# project2.net
KiCad netlist of a schematic drawn in Altium Designer
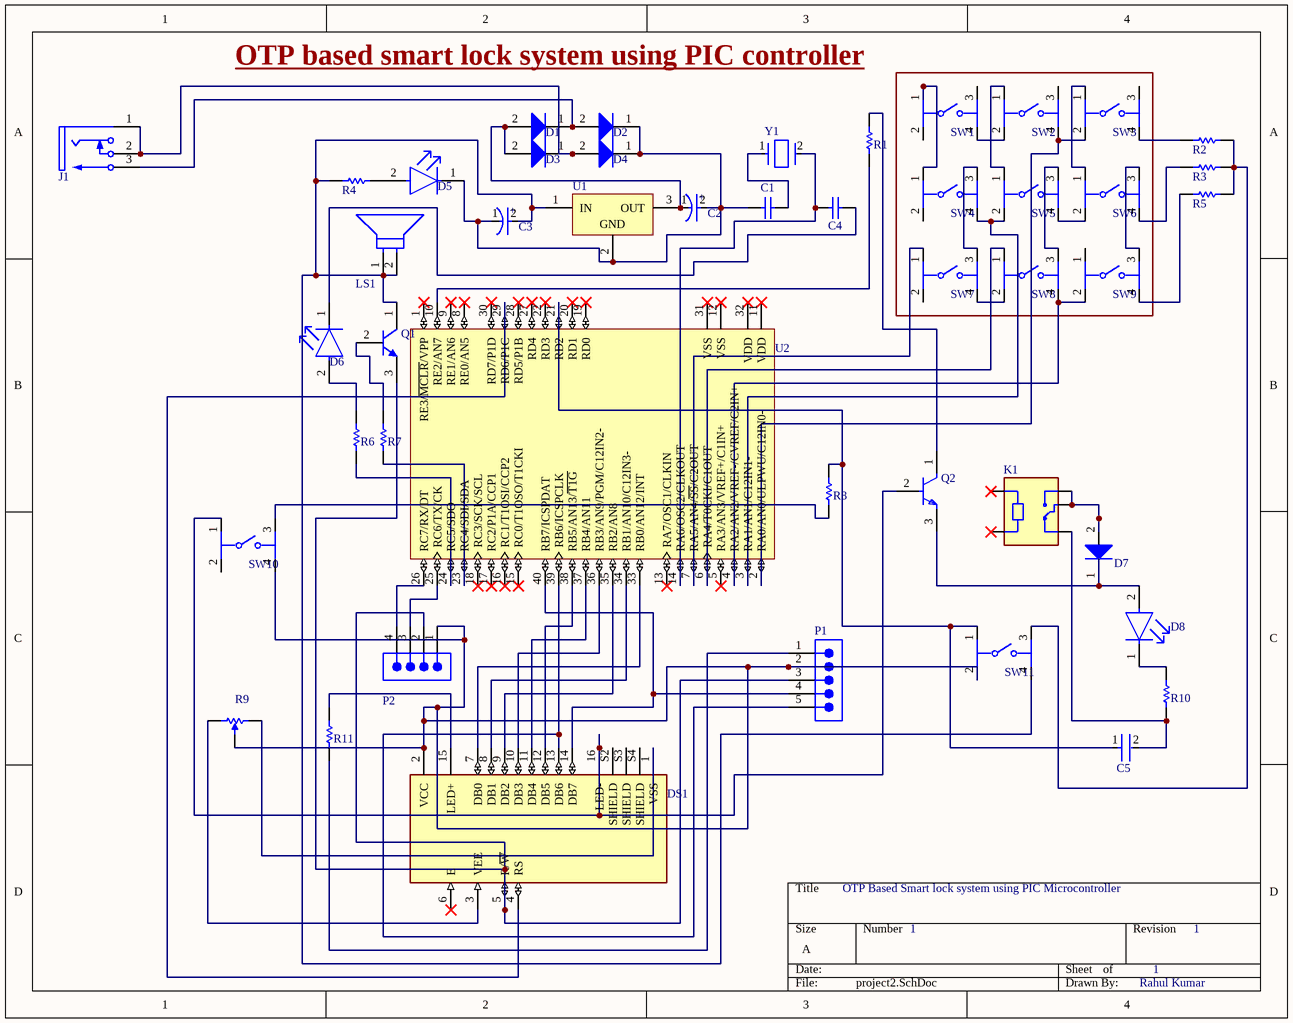
[diagram p0: project2.SchDoc]

(export (version "E")
  (design (tool "Eeschema 10.0.6"))
  (components
    (comp (ref "C1")
      (value "GRM188R71H102KA01D")
      (footprint "CAPC1608X90X35NL10T15")
      (fields (field (name "MANUFACTURER") "Murata"))
      (libsource (lib "Altium Content Vault") (part "CAP"))
    )
    (comp (ref "C2")
      (value "EEUFM1V221L")
      (footprint "FP-RAD-TH-D_8_0_5-L_15_1-MFG")
      (description "Aluminum Electrolytic Capacitors (Radial Lead Type) 220uF ±20% 35V")
      (fields (field (name "TOLERANCE") "20%") (field (name "VOLTAGE") "35V"))
      (libsource (lib "Altium Content Vault") (part "a00bbbee19879c290e62620ae7e47b1"))
    )
    (comp (ref "C3")
      (value "EEUHD1E101")
      (footprint "FP-RAD-TH-D_6_3_0_5-L_11-MFG")
      (description "Aluminum Electrolytic Capacitors (Radial Lead Type) AEC-Q200 Qualified 100uF ±20% 25V")
      (fields (field (name "TOLERANCE") "20%") (field (name "VOLTAGE") "25V"))
      (libsource (lib "Altium Content Vault") (part "a00bbbee19879c290e62620ae7e47b1"))
    )
    (comp (ref "C4")
      (value "GRM188R71H102KA01D")
      (footprint "CAPC1608X90X35NL10T15")
      (fields (field (name "MANUFACTURER") "Murata"))
      (libsource (lib "Altium Content Vault") (part "CAP"))
    )
    (comp (ref "C5")
      (value "06035A221JAT2A")
      (footprint "FP-0603-L_1_6_0_15-W_0_81-IPC_B")
      (description "General Purpose Ceramic Capacitor, 0603, 220pF, 5%, NP0, 30ppm/°C, 50V")
      (fields (field (name "TOLERANCE") "5%") (field (name "VOLTAGE") "50V"))
      (libsource (lib "Altium Content Vault") (part "02cd4be3c70576c341d710602a673aa"))
    )
    (comp (ref "D1")
      (value "BAT54HT1G")
      (footprint "ONSC-SOD-323-2-477-02_V")
      (description "Schottky Barrier Diode, 2-Pin SOD-323, Pb-Free, Tape and Reel")
      (fields (field (name "MANUFACTURER") "On Semiconductor"))
      (libsource (lib "Altium Content Vault") (part "ONSC-D-K1A2-2"))
    )
    (comp (ref "D2")
      (value "BAT54HT1G")
      (footprint "ONSC-SOD-323-2-477-02_V")
      (description "Schottky Barrier Diode, 2-Pin SOD-323, Pb-Free, Tape and Reel")
      (fields (field (name "MANUFACTURER") "On Semiconductor"))
      (libsource (lib "Altium Content Vault") (part "ONSC-D-K1A2-2"))
    )
    (comp (ref "D3")
      (value "BAT54HT1G")
      (footprint "ONSC-SOD-323-2-477-02_V")
      (description "Schottky Barrier Diode, 2-Pin SOD-323, Pb-Free, Tape and Reel")
      (fields (field (name "MANUFACTURER") "On Semiconductor"))
      (libsource (lib "Altium Content Vault") (part "ONSC-D-K1A2-2"))
    )
    (comp (ref "D4")
      (value "BAT54HT1G")
      (footprint "ONSC-SOD-323-2-477-02_V")
      (description "Schottky Barrier Diode, 2-Pin SOD-323, Pb-Free, Tape and Reel")
      (fields (field (name "MANUFACTURER") "On Semiconductor"))
      (libsource (lib "Altium Content Vault") (part "ONSC-D-K1A2-2"))
    )
    (comp (ref "D5")
      (value "LTST-C190GKT")
      (footprint "FP-LTST-C190GKT-MFG")
      (description "LED GREEN CLEAR CHIP SMD")
      (fields (field (name "VOLTAGE") "2V"))
      (libsource (lib "Altium Content Vault") (part "8706943c75ba83719d021d2fdc84c58"))
    )
    (comp (ref "D6")
      (value "LTST-C190GKT")
      (footprint "FP-LTST-C190GKT-MFG")
      (description "LED GREEN CLEAR CHIP SMD")
      (fields (field (name "VOLTAGE") "2V"))
      (libsource (lib "Altium Content Vault") (part "8706943c75ba83719d021d2fdc84c58"))
    )
    (comp (ref "D7")
      (value "BAT54HT1G")
      (footprint "ONSC-SOD-323-2-477-02_V")
      (description "Schottky Barrier Diode, 2-Pin SOD-323, Pb-Free, Tape and Reel")
      (fields (field (name "MANUFACTURER") "On Semiconductor"))
      (libsource (lib "Altium Content Vault") (part "ONSC-D-K1A2-2"))
    )
    (comp (ref "D8")
      (value "LTST-C190GKT")
      (footprint "FP-LTST-C190GKT-MFG")
      (description "LED GREEN CLEAR CHIP SMD")
      (fields (field (name "VOLTAGE") "2V"))
      (libsource (lib "Altium Content Vault") (part "8706943c75ba83719d021d2fdc84c58"))
    )
    (comp (ref "DS1")
      (value "RC1602B-BIW-CSV")
      (footprint "LCD_RC1602B-BIW-CSV")
      (description "Display: LCD; alphanumeric; STN Negative; 16x2; blue; LED; PIN: 16")
      (fields (field (name "MF") "Raystar"))
      (libsource (lib "RC1602B-BIW-CSV") (part "RC1602B-BIW-CSV"))
    )
    (comp (ref "J1")
      (value "RAPC712X")
      (footprint "SWITCH-RAPC712X-3_V")
      (description "Conn Powerjack Mini R/A PCMT, 5 A, 3-Pin THD, RoHS")
      (fields (field (name "MANUFACTURER") "Switchcraft"))
      (libsource (lib "Altium Content Vault") (part "SWITCH-RAPC712X-3"))
    )
    (comp (ref "K1")
      (value "SRD-05VDC-SL-C")
      (footprint "RELAY_SRD-05VDC-SL-C")
      (fields (field (name "MF") "Songle Relay"))
      (libsource (lib "SRD-05VDC-SL-C") (part "SRD-05VDC-SL-C"))
    )
    (comp (ref "LS1")
      (value "PKM17EPPH4001-B0")
      (footprint "FP-PKM17EPPH4001-B0-MFG")
      (description "AUDIO PIEZO TRANSDUCER 25V TH")
      (libsource (lib "Altium Content Vault") (part "5f581d31613f872430949aa526fd155"))
    )
    (comp (ref "P1")
      (value "653105124022")
      (footprint "653105124022")
      (libsource (lib "Altium Content Vault") (part "Header_Male_1R_05P"))
    )
    (comp (ref "P2")
      (value "679304124022")
      (footprint "679304124022")
      (libsource (lib "Altium Content Vault") (part "Header_Male_1R_04P"))
    )
    (comp (ref "Q1")
      (value "BC547B")
      (footprint "ONSC-TO-92-3-29-11")
      (description "Amplifier Transistor, NPN Silicon, 3-Pin TO-92, Bulk Box")
      (fields (field (name "MANUFACTURER") "On Semiconductor"))
      (libsource (lib "Altium Content Vault") (part "ONSC-NPN-C1B2E3-3"))
    )
    (comp (ref "Q2")
      (value "BC548")
      (footprint "FP-135AN-MFG")
      (description "BC548 Bulk Through Hole NPN Single Bipolar (BJT) Transistor 110 @ 2mA 5V 100mA 500mW 300MHz")
      (libsource (lib "Altium Content Vault") (part "0e34aa19c3f436cc9ae3cb3686437ec"))
    )
    (comp (ref "R1")
      (value "ERJ-8GEY0R00V")
      (footprint "RESC3216X70X50NL05T20")
      (fields (field (name "MANUFACTURER") "Panasonic"))
      (libsource (lib "Altium Content Vault") (part "RES"))
    )
    (comp (ref "R2")
      (value "ERJ-8GEY0R00V")
      (footprint "RESC3216X70X50NL05T20")
      (fields (field (name "MANUFACTURER") "Panasonic"))
      (libsource (lib "Altium Content Vault") (part "RES"))
    )
    (comp (ref "R3")
      (value "ERJ-8GEY0R00V")
      (footprint "RESC3216X70X50NL05T20")
      (fields (field (name "MANUFACTURER") "Panasonic"))
      (libsource (lib "Altium Content Vault") (part "RES"))
    )
    (comp (ref "R4")
      (value "ERJ-8GEY0R00V")
      (footprint "RESC3216X70X50NL05T20")
      (fields (field (name "MANUFACTURER") "Panasonic"))
      (libsource (lib "Altium Content Vault") (part "RES"))
    )
    (comp (ref "R5")
      (value "ERJ-8GEY0R00V")
      (footprint "RESC3216X70X50NL05T20")
      (fields (field (name "MANUFACTURER") "Panasonic"))
      (libsource (lib "Altium Content Vault") (part "RES"))
    )
    (comp (ref "R6")
      (value "ERJ-8GEY0R00V")
      (footprint "RESC3216X70X50NL05T20")
      (fields (field (name "MANUFACTURER") "Panasonic"))
      (libsource (lib "Altium Content Vault") (part "RES"))
    )
    (comp (ref "R7")
      (value "ERJ-8GEY0R00V")
      (footprint "RESC3216X70X50NL05T20")
      (fields (field (name "MANUFACTURER") "Panasonic"))
      (libsource (lib "Altium Content Vault") (part "RES"))
    )
    (comp (ref "R8")
      (value "ERJ-8GEY0R00V")
      (footprint "RESC3216X70X50NL05T20")
      (fields (field (name "MANUFACTURER") "Panasonic"))
      (libsource (lib "Altium Content Vault") (part "RES"))
    )
    (comp (ref "R9")
      (value "3296W-1-102LF")
      (footprint "BOUR-3296W-1-3")
      (description "Square Trimpot(R) Trimming Potentiometer, 1000 Ohm, -55 to 125 degC, 3-Pin THD, RoHS, Tube")
      (fields (field (name "TOLERANCE") "1%"))
      (libsource (lib "Altium Content Vault") (part "RES-ADJ-3"))
    )
    (comp (ref "R10")
      (value "ERJ-8GEY0R00V")
      (footprint "RESC3216X70X50NL05T20")
      (fields (field (name "MANUFACTURER") "Panasonic"))
      (libsource (lib "Altium Content Vault") (part "RES"))
    )
    (comp (ref "R11")
      (value "ERJ-8GEY0R00V")
      (footprint "RESC3216X70X50NL05T20")
      (fields (field (name "MANUFACTURER") "Panasonic"))
      (libsource (lib "Altium Content Vault") (part "RES"))
    )
    (comp (ref "SW1")
      (value "1-1825910-4")
      (footprint "FP-1-1825910-4-MFG")
      (description "SWITCH TACTILE SPST-NO 0.05A 24V")
      (fields
        (field (name "OCTOPART") "https://octopart.com/1-1825910-4-te+connectivity-42270468")
        (field (name "MANUFACTURER") "TE Connectivity")
      )
      (libsource (lib "Altium Content Vault") (part "b8895f3f4cefb76e1819d2863dba89b"))
    )
    (comp (ref "SW2")
      (value "1-1825910-4")
      (footprint "FP-1-1825910-4-MFG")
      (description "SWITCH TACTILE SPST-NO 0.05A 24V")
      (fields
        (field (name "OCTOPART") "https://octopart.com/1-1825910-4-te+connectivity-42270468")
        (field (name "MANUFACTURER") "TE Connectivity")
      )
      (libsource (lib "Altium Content Vault") (part "b8895f3f4cefb76e1819d2863dba89b"))
    )
    (comp (ref "SW3")
      (value "1-1825910-4")
      (footprint "FP-1-1825910-4-MFG")
      (description "SWITCH TACTILE SPST-NO 0.05A 24V")
      (fields
        (field (name "OCTOPART") "https://octopart.com/1-1825910-4-te+connectivity-42270468")
        (field (name "MANUFACTURER") "TE Connectivity")
      )
      (libsource (lib "Altium Content Vault") (part "b8895f3f4cefb76e1819d2863dba89b"))
    )
    (comp (ref "SW4")
      (value "1-1825910-4")
      (footprint "FP-1-1825910-4-MFG")
      (description "SWITCH TACTILE SPST-NO 0.05A 24V")
      (fields
        (field (name "OCTOPART") "https://octopart.com/1-1825910-4-te+connectivity-42270468")
        (field (name "MANUFACTURER") "TE Connectivity")
      )
      (libsource (lib "Altium Content Vault") (part "b8895f3f4cefb76e1819d2863dba89b"))
    )
    (comp (ref "SW5")
      (value "1-1825910-4")
      (footprint "FP-1-1825910-4-MFG")
      (description "SWITCH TACTILE SPST-NO 0.05A 24V")
      (fields
        (field (name "OCTOPART") "https://octopart.com/1-1825910-4-te+connectivity-42270468")
        (field (name "MANUFACTURER") "TE Connectivity")
      )
      (libsource (lib "Altium Content Vault") (part "b8895f3f4cefb76e1819d2863dba89b"))
    )
    (comp (ref "SW6")
      (value "1-1825910-4")
      (footprint "FP-1-1825910-4-MFG")
      (description "SWITCH TACTILE SPST-NO 0.05A 24V")
      (fields
        (field (name "OCTOPART") "https://octopart.com/1-1825910-4-te+connectivity-42270468")
        (field (name "MANUFACTURER") "TE Connectivity")
      )
      (libsource (lib "Altium Content Vault") (part "b8895f3f4cefb76e1819d2863dba89b"))
    )
    (comp (ref "SW7")
      (value "1-1825910-4")
      (footprint "FP-1-1825910-4-MFG")
      (description "SWITCH TACTILE SPST-NO 0.05A 24V")
      (fields
        (field (name "OCTOPART") "https://octopart.com/1-1825910-4-te+connectivity-42270468")
        (field (name "MANUFACTURER") "TE Connectivity")
      )
      (libsource (lib "Altium Content Vault") (part "b8895f3f4cefb76e1819d2863dba89b"))
    )
    (comp (ref "SW8")
      (value "1-1825910-4")
      (footprint "FP-1-1825910-4-MFG")
      (description "SWITCH TACTILE SPST-NO 0.05A 24V")
      (fields
        (field (name "OCTOPART") "https://octopart.com/1-1825910-4-te+connectivity-42270468")
        (field (name "MANUFACTURER") "TE Connectivity")
      )
      (libsource (lib "Altium Content Vault") (part "b8895f3f4cefb76e1819d2863dba89b"))
    )
    (comp (ref "SW9")
      (value "1-1825910-4")
      (footprint "FP-1-1825910-4-MFG")
      (description "SWITCH TACTILE SPST-NO 0.05A 24V")
      (fields
        (field (name "OCTOPART") "https://octopart.com/1-1825910-4-te+connectivity-42270468")
        (field (name "MANUFACTURER") "TE Connectivity")
      )
      (libsource (lib "Altium Content Vault") (part "b8895f3f4cefb76e1819d2863dba89b"))
    )
    (comp (ref "SW10")
      (value "1-1825910-4")
      (footprint "FP-1-1825910-4-MFG")
      (description "SWITCH TACTILE SPST-NO 0.05A 24V")
      (fields
        (field (name "OCTOPART") "https://octopart.com/1-1825910-4-te+connectivity-42270468")
        (field (name "MANUFACTURER") "TE Connectivity")
      )
      (libsource (lib "Altium Content Vault") (part "b8895f3f4cefb76e1819d2863dba89b"))
    )
    (comp (ref "SW11")
      (value "1-1825910-4")
      (footprint "FP-1-1825910-4-MFG")
      (description "SWITCH TACTILE SPST-NO 0.05A 24V")
      (fields
        (field (name "OCTOPART") "https://octopart.com/1-1825910-4-te+connectivity-42270468")
        (field (name "MANUFACTURER") "TE Connectivity")
      )
      (libsource (lib "Altium Content Vault") (part "b8895f3f4cefb76e1819d2863dba89b"))
    )
    (comp (ref "U1")
      (value "L7805CV")
      (footprint "TO220")
      (description "Positive Voltage Regulator, 5V, 3-Pin TO-220")
      (libsource (lib "Altium Content Vault") (part "PM-REG-L4940-SIL3"))
    )
    (comp (ref "U2")
      (value "PIC16F887-I/P")
      (footprint "PDIP600-P40")
      (libsource (lib "Altium Content Vault") (part "MC-8B-16F884-IL40"))
    )
    (comp (ref "Y1")
      (value "ABLS-8.000MHZ-B2-T")
      (footprint "FP-ABLS-MFG")
      (description "CRYSTAL 8.0000MHZ 18PF SMD")
      (fields (field (name "TOLERANCE") "20ppm"))
      (libsource (lib "Altium Content Vault") (part "c23a69dc6c9e2f18f2079038eb95dd1"))
    )
  )
  (nets
    (net (code "1") (name "Net-(C1-Pad2)") (class "Default")
      (node (ref "C1") (pin "2") (pinfunction "2_2") (pintype "passive"))
      (node (ref "Y1") (pin "1") (pinfunction "1_1") (pintype "passive"))
    )
    (net (code "2") (name "Net-(C2-A)") (class "Default")
      (node (ref "C1") (pin "1") (pinfunction "1_1") (pintype "passive"))
      (node (ref "C2") (pin "2") (pinfunction "A_2") (pintype "passive"))
      (node (ref "C3") (pin "1") (pinfunction "C_1") (pintype "passive"))
      (node (ref "D2") (pin "1") (pinfunction "K_1") (pintype "passive"))
      (node (ref "D4") (pin "1") (pinfunction "K_1") (pintype "passive"))
      (node (ref "D5") (pin "1") (pinfunction "C_1") (pintype "passive"))
      (node (ref "U1") (pin "2") (pinfunction "GND_2") (pintype "power_in"))
    )
    (net (code "3") (name "Net-(C2-C)") (class "Default")
      (node (ref "C2") (pin "1") (pinfunction "C_1") (pintype "passive"))
      (node (ref "D1") (pin "2") (pinfunction "A_2") (pintype "passive"))
      (node (ref "D3") (pin "2") (pinfunction "A_2") (pintype "passive"))
      (node (ref "U1") (pin "3") (pinfunction "OUT_3") (pintype "power_in"))
    )
    (net (code "4") (name "Net-(C3-A)") (class "Default")
      (node (ref "C3") (pin "2") (pinfunction "A_2") (pintype "passive"))
      (node (ref "LS1") (pin "1") (pinfunction "1_1") (pintype "passive"))
      (node (ref "LS1") (pin "2") (pinfunction "2_2") (pintype "passive"))
      (node (ref "Q1") (pin "1") (pinfunction "C_1") (pintype "passive"))
      (node (ref "R4") (pin "2") (pinfunction "2_2") (pintype "passive"))
      (node (ref "SW11") (pin "4") (pinfunction "4_4") (pintype "passive"))
      (node (ref "U1") (pin "1") (pinfunction "IN_1") (pintype "power_in"))
    )
    (net (code "5") (name "Net-(C5-Pad2)") (class "Default")
      (node (ref "C5") (pin "2") (pinfunction "2_2") (pintype "passive"))
      (node (ref "K1") (pin "NC") (pinfunction "NC_NC") (pintype "passive"))
      (node (ref "R10") (pin "1") (pinfunction "1_1") (pintype "passive"))
    )
    (net (code "6") (name "Net-(D1-K)") (class "Default")
      (node (ref "D1") (pin "1") (pinfunction "K_1") (pintype "passive"))
      (node (ref "D2") (pin "2") (pinfunction "A_2") (pintype "passive"))
      (node (ref "J1") (pin "3") (pinfunction "3_3") (pintype "passive"))
    )
    (net (code "7") (name "Net-(D3-K)") (class "Default")
      (node (ref "D3") (pin "1") (pinfunction "K_1") (pintype "passive"))
      (node (ref "D4") (pin "2") (pinfunction "A_2") (pintype "passive"))
      (node (ref "J1") (pin "1") (pinfunction "1_1") (pintype "passive"))
      (node (ref "J1") (pin "2") (pinfunction "2_2") (pintype "passive"))
    )
    (net (code "8") (name "Net-(D5-A)") (class "Default")
      (node (ref "D5") (pin "2") (pinfunction "A_2") (pintype "passive"))
      (node (ref "R4") (pin "1") (pinfunction "1_1") (pintype "passive"))
    )
    (net (code "9") (name "Net-(D6-A)") (class "Default")
      (node (ref "D6") (pin "2") (pinfunction "A_2") (pintype "passive"))
      (node (ref "R6") (pin "2") (pinfunction "2_2") (pintype "passive"))
    )
    (net (code "10") (name "Net-(D6-C)") (class "Default")
      (node (ref "C4") (pin "1") (pinfunction "1_1") (pintype "passive"))
      (node (ref "D6") (pin "1") (pinfunction "C_1") (pintype "passive"))
    )
    (net (code "11") (name "Net-(D7-A)") (class "Default")
      (node (ref "D7") (pin "2") (pinfunction "A_2") (pintype "passive"))
      (node (ref "K1") (pin "COM") (pinfunction "COM_COM") (pintype "passive"))
      (node (ref "K1") (pin "NO") (pinfunction "NO_NO") (pintype "passive"))
    )
    (net (code "12") (name "Net-(D7-K)") (class "Default")
      (node (ref "D7") (pin "1") (pinfunction "K_1") (pintype "passive"))
      (node (ref "D8") (pin "2") (pinfunction "A_2") (pintype "passive"))
      (node (ref "Q2") (pin "3") (pinfunction "E_3") (pintype "passive"))
    )
    (net (code "13") (name "Net-(D8-C)") (class "Default")
      (node (ref "D8") (pin "1") (pinfunction "C_1") (pintype "passive"))
      (node (ref "R10") (pin "2") (pinfunction "2_2") (pintype "passive"))
    )
    (net (code "14") (name "Net-(DS1-DB0)") (class "Default")
      (node (ref "DS1") (pin "7") (pinfunction "DB0_7") (pintype "bidirectional"))
      (node (ref "U2") (pin "33") (pinfunction "RB0/AN12/INT_33") (pintype "bidirectional"))
    )
    (net (code "15") (name "Net-(DS1-DB1)") (class "Default")
      (node (ref "DS1") (pin "8") (pinfunction "DB1_8") (pintype "bidirectional"))
      (node (ref "U2") (pin "34") (pinfunction "RB1/AN10/C12IN3-_34") (pintype "bidirectional"))
    )
    (net (code "16") (name "Net-(DS1-DB2)") (class "Default")
      (node (ref "DS1") (pin "9") (pinfunction "DB2_9") (pintype "bidirectional"))
      (node (ref "U2") (pin "35") (pinfunction "RB2/AN8_35") (pintype "bidirectional"))
    )
    (net (code "17") (name "Net-(DS1-DB3)") (class "Default")
      (node (ref "DS1") (pin "10") (pinfunction "DB3_10") (pintype "bidirectional"))
      (node (ref "U2") (pin "36") (pinfunction "RB3/AN9/PGM/C12IN2-_36") (pintype "bidirectional"))
    )
    (net (code "18") (name "Net-(DS1-DB4)") (class "Default")
      (node (ref "DS1") (pin "11") (pinfunction "DB4_11") (pintype "bidirectional"))
      (node (ref "U2") (pin "37") (pinfunction "RB4/AN11_37") (pintype "bidirectional"))
    )
    (net (code "19") (name "Net-(DS1-DB5)") (class "Default")
      (node (ref "DS1") (pin "12") (pinfunction "DB5_12") (pintype "bidirectional"))
      (node (ref "U2") (pin "38") (pinfunction "RB5/AN13/~{T1G}_38") (pintype "bidirectional"))
    )
    (net (code "20") (name "Net-(DS1-DB6)") (class "Default")
      (node (ref "DS1") (pin "13") (pinfunction "DB6_13") (pintype "bidirectional"))
      (node (ref "P1") (pin "5") (pinfunction "5_5") (pintype "passive"))
      (node (ref "U2") (pin "39") (pinfunction "RB6/ICSPCLK_39") (pintype "bidirectional"))
    )
    (net (code "21") (name "Net-(DS1-DB7)") (class "Default")
      (node (ref "DS1") (pin "14") (pinfunction "DB7_14") (pintype "bidirectional"))
      (node (ref "P1") (pin "4") (pinfunction "4_4") (pintype "passive"))
      (node (ref "U2") (pin "40") (pinfunction "RB7/ICSPDAT_40") (pintype "bidirectional"))
    )
    (net (code "22") (name "Net-(DS1-LED+)") (class "Default")
      (node (ref "DS1") (pin "15") (pinfunction "LED+_15") (pintype "power_in"))
      (node (ref "R11") (pin "2") (pinfunction "2_2") (pintype "passive"))
    )
    (net (code "23") (name "Net-(DS1-LED-)") (class "Default")
      (node (ref "DS1") (pin "16") (pinfunction "LED-_16") (pintype "power_in"))
      (node (ref "Q2") (pin "2") (pinfunction "B_2") (pintype "passive"))
      (node (ref "SW10") (pin "1") (pinfunction "1_1") (pintype "passive"))
    )
    (net (code "24") (name "Net-(DS1-RS)") (class "Default")
      (node (ref "DS1") (pin "4") (pinfunction "RS_4") (pintype "bidirectional"))
      (node (ref "U2") (pin "29") (pinfunction "RD6/P1C_29") (pintype "bidirectional"))
    )
    (net (code "25") (name "Net-(DS1-R{slash}~{W})") (class "Default")
      (node (ref "DS1") (pin "5") (pinfunction "R/~{W}_5") (pintype "bidirectional"))
      (node (ref "P1") (pin "3") (pinfunction "3_3") (pintype "passive"))
      (node (ref "P2") (pin "2") (pinfunction "2_2") (pintype "passive"))
      (node (ref "Q1") (pin "3") (pinfunction "E_3") (pintype "passive"))
    )
    (net (code "26") (name "Net-(DS1-VCC)") (class "Default")
      (node (ref "DS1") (pin "2") (pinfunction "VCC_2") (pintype "power_in"))
      (node (ref "P1") (pin "2") (pinfunction "2_2") (pintype "passive"))
      (node (ref "P2") (pin "1") (pinfunction "1_1") (pintype "passive"))
      (node (ref "R9") (pin "3") (pinfunction "TAP_3") (pintype "passive"))
      (node (ref "SW10") (pin "4") (pinfunction "4_4") (pintype "passive"))
      (node (ref "SW11") (pin "2") (pinfunction "2_2") (pintype "passive"))
    )
    (net (code "27") (name "Net-(DS1-VEE)") (class "Default")
      (node (ref "DS1") (pin "3") (pinfunction "VEE_3") (pintype "input"))
      (node (ref "R9") (pin "1") (pinfunction "A_1") (pintype "passive"))
    )
    (net (code "28") (name "Net-(DS1-VSS)") (class "Default")
      (node (ref "DS1") (pin "1") (pinfunction "VSS_1") (pintype "power_in"))
      (node (ref "R9") (pin "2") (pinfunction "B_2") (pintype "passive"))
    )
    (net (code "29") (name "Net-(P1-Pad1)") (class "Default")
      (node (ref "P1") (pin "1") (pinfunction "1_1") (pintype "passive"))
      (node (ref "R11") (pin "1") (pinfunction "1_1") (pintype "passive"))
    )
    (net (code "30") (name "Net-(Q1-B)") (class "Default")
      (node (ref "Q1") (pin "2") (pinfunction "B_2") (pintype "passive"))
      (node (ref "R7") (pin "2") (pinfunction "2_2") (pintype "passive"))
    )
    (net (code "31") (name "Net-(Q2-C)") (class "Default")
      (node (ref "Q2") (pin "1") (pinfunction "C_1") (pintype "passive"))
      (node (ref "R1") (pin "1") (pinfunction "1_1") (pintype "passive"))
    )
    (net (code "32") (name "Net-(R2-Pad1)") (class "Default")
      (node (ref "R2") (pin "1") (pinfunction "1_1") (pintype "passive"))
      (node (ref "R3") (pin "1") (pinfunction "1_1") (pintype "passive"))
      (node (ref "R5") (pin "1") (pinfunction "1_1") (pintype "passive"))
      (node (ref "SW11") (pin "3") (pinfunction "3_3") (pintype "passive"))
    )
    (net (code "33") (name "Net-(R2-Pad2)") (class "Default")
      (node (ref "R2") (pin "2") (pinfunction "2_2") (pintype "passive"))
      (node (ref "SW3") (pin "4") (pinfunction "4_4") (pintype "passive"))
    )
    (net (code "34") (name "Net-(R3-Pad2)") (class "Default")
      (node (ref "R3") (pin "2") (pinfunction "2_2") (pintype "passive"))
      (node (ref "SW6") (pin "4") (pinfunction "4_4") (pintype "passive"))
    )
    (net (code "35") (name "Net-(R5-Pad2)") (class "Default")
      (node (ref "R5") (pin "2") (pinfunction "2_2") (pintype "passive"))
      (node (ref "SW9") (pin "4") (pinfunction "4_4") (pintype "passive"))
    )
    (net (code "36") (name "Net-(R8-Pad1)") (class "Default")
      (node (ref "R8") (pin "1") (pinfunction "1_1") (pintype "passive"))
      (node (ref "SW10") (pin "3") (pinfunction "3_3") (pintype "passive"))
    )
    (net (code "37") (name "Net-(SW1-Pad1)") (class "Default")
      (node (ref "SW1") (pin "1") (pinfunction "1_1") (pintype "passive"))
      (node (ref "SW4") (pin "1") (pinfunction "1_1") (pintype "passive"))
    )
    (net (code "38") (name "Net-(SW1-Pad4)") (class "Default")
      (node (ref "SW1") (pin "4") (pinfunction "4_4") (pintype "passive"))
      (node (ref "SW2") (pin "2") (pinfunction "2_2") (pintype "passive"))
    )
    (net (code "39") (name "Net-(SW2-Pad1)") (class "Default")
      (node (ref "SW2") (pin "1") (pinfunction "1_1") (pintype "passive"))
      (node (ref "SW5") (pin "1") (pinfunction "1_1") (pintype "passive"))
    )
    (net (code "40") (name "Net-(SW3-Pad1)") (class "Default")
      (node (ref "SW3") (pin "1") (pinfunction "1_1") (pintype "passive"))
      (node (ref "SW6") (pin "1") (pinfunction "1_1") (pintype "passive"))
    )
    (net (code "41") (name "Net-(SW4-Pad3)") (class "Default")
      (node (ref "SW4") (pin "3") (pinfunction "3_3") (pintype "passive"))
      (node (ref "SW7") (pin "3") (pinfunction "3_3") (pintype "passive"))
    )
    (net (code "42") (name "Net-(SW5-Pad3)") (class "Default")
      (node (ref "SW5") (pin "3") (pinfunction "3_3") (pintype "passive"))
      (node (ref "SW8") (pin "3") (pinfunction "3_3") (pintype "passive"))
    )
    (net (code "43") (name "Net-(SW5-Pad4)") (class "Default")
      (node (ref "SW5") (pin "4") (pinfunction "4_4") (pintype "passive"))
      (node (ref "SW6") (pin "2") (pinfunction "2_2") (pintype "passive"))
    )
    (net (code "44") (name "Net-(SW6-Pad3)") (class "Default")
      (node (ref "SW6") (pin "3") (pinfunction "3_3") (pintype "passive"))
      (node (ref "SW9") (pin "3") (pinfunction "3_3") (pintype "passive"))
    )
    (net (code "45") (name "Net-(SW7-Pad4)") (class "Default")
      (node (ref "SW7") (pin "4") (pinfunction "4_4") (pintype "passive"))
      (node (ref "SW8") (pin "2") (pinfunction "2_2") (pintype "passive"))
    )
    (net (code "46") (name "Net-(U2-RA0{slash}AN0{slash}ULPWU{slash}C12IN0-)") (class "Default")
      (node (ref "SW2") (pin "4") (pinfunction "4_4") (pintype "passive"))
      (node (ref "SW3") (pin "2") (pinfunction "2_2") (pintype "passive"))
      (node (ref "U2") (pin "2") (pinfunction "RA0/AN0/ULPWU/C12IN0-_2") (pintype "bidirectional"))
    )
    (net (code "47") (name "Net-(U2-RA1{slash}AN1{slash}C12IN1-)") (class "Default")
      (node (ref "SW4") (pin "4") (pinfunction "4_4") (pintype "passive"))
      (node (ref "SW5") (pin "2") (pinfunction "2_2") (pintype "passive"))
      (node (ref "U2") (pin "3") (pinfunction "RA1/AN1/C12IN1-_3") (pintype "bidirectional"))
    )
    (net (code "48") (name "Net-(U2-RA2{slash}AN2{slash}VREF-{slash}CVREF{slash}C2IN+)") (class "Default")
      (node (ref "SW8") (pin "4") (pinfunction "4_4") (pintype "passive"))
      (node (ref "SW9") (pin "2") (pinfunction "2_2") (pintype "passive"))
      (node (ref "U2") (pin "4") (pinfunction "RA2/AN2/VREF-/CVREF/C2IN+_4") (pintype "bidirectional"))
    )
    (net (code "49") (name "Net-(U2-RA4{slash}T0CKI{slash}C1OUT)") (class "Default")
      (node (ref "SW8") (pin "1") (pinfunction "1_1") (pintype "passive"))
      (node (ref "U2") (pin "6") (pinfunction "RA4/T0CKI/C1OUT_6") (pintype "bidirectional"))
    )
    (net (code "50") (name "Net-(U2-RA5{slash}AN4{slash}~{SS}{slash}C2OUT)") (class "Default")
      (node (ref "SW7") (pin "1") (pinfunction "1_1") (pintype "passive"))
      (node (ref "U2") (pin "7") (pinfunction "RA5/AN4/~{SS}/C2OUT_7") (pintype "bidirectional"))
    )
    (net (code "51") (name "Net-(U2-RA6{slash}OSC2{slash}CLKOUT)") (class "Default")
      (node (ref "C4") (pin "2") (pinfunction "2_2") (pintype "passive"))
      (node (ref "U2") (pin "14") (pinfunction "RA6/OSC2/CLKOUT_14") (pintype "bidirectional"))
      (node (ref "Y1") (pin "2") (pinfunction "2_2") (pintype "passive"))
    )
    (net (code "52") (name "Net-(U2-RC4{slash}SDI{slash}SDA)") (class "Default")
      (node (ref "R7") (pin "1") (pinfunction "1_1") (pintype "passive"))
      (node (ref "U2") (pin "23") (pinfunction "RC4/SDI/SDA_23") (pintype "bidirectional"))
    )
    (net (code "53") (name "Net-(U2-RC5{slash}SDO)") (class "Default")
      (node (ref "R6") (pin "1") (pinfunction "1_1") (pintype "passive"))
      (node (ref "U2") (pin "24") (pinfunction "RC5/SDO_24") (pintype "bidirectional"))
    )
    (net (code "54") (name "Net-(U2-RC6{slash}TX{slash}CK)") (class "Default")
      (node (ref "P2") (pin "3") (pinfunction "3_3") (pintype "passive"))
      (node (ref "U2") (pin "25") (pinfunction "RC6/TX/CK_25") (pintype "bidirectional"))
    )
    (net (code "55") (name "Net-(U2-RC7{slash}RX{slash}DT)") (class "Default")
      (node (ref "P2") (pin "4") (pinfunction "4_4") (pintype "passive"))
      (node (ref "U2") (pin "26") (pinfunction "RC7/RX/DT_26") (pintype "bidirectional"))
    )
    (net (code "56") (name "Net-(U2-RD2)") (class "Default")
      (node (ref "C5") (pin "1") (pinfunction "1_1") (pintype "passive"))
      (node (ref "R8") (pin "2") (pinfunction "2_2") (pintype "passive"))
      (node (ref "SW11") (pin "1") (pinfunction "1_1") (pintype "passive"))
      (node (ref "U2") (pin "21") (pinfunction "RD2_21") (pintype "bidirectional"))
    )
    (net (code "57") (name "Net-(U2-RE2{slash}AN7)") (class "Default")
      (node (ref "R1") (pin "2") (pinfunction "2_2") (pintype "passive"))
      (node (ref "U2") (pin "10") (pinfunction "RE2/AN7_10") (pintype "bidirectional"))
    )
    (net (code "58") (name "unconnected-(DS1-E-Pad6)") (class "Default")
      (node (ref "DS1") (pin "6") (pinfunction "E_6") (pintype "input+no_connect"))
    )
    (net (code "59") (name "unconnected-(DS1-SHIELD-PadS2)") (class "Default")
      (node (ref "DS1") (pin "S2") (pinfunction "SHIELD_S2") (pintype "passive"))
    )
    (net (code "60") (name "unconnected-(DS1-SHIELD-PadS3)") (class "Default")
      (node (ref "DS1") (pin "S3") (pinfunction "SHIELD_S3") (pintype "passive"))
    )
    (net (code "61") (name "unconnected-(DS1-SHIELD-PadS4)") (class "Default")
      (node (ref "DS1") (pin "S4") (pinfunction "SHIELD_S4") (pintype "passive"))
    )
    (net (code "62") (name "unconnected-(K1-PadA1)") (class "Default")
      (node (ref "K1") (pin "A1") (pinfunction "A1_A1") (pintype "passive+no_connect"))
    )
    (net (code "63") (name "unconnected-(K1-PadA2)") (class "Default")
      (node (ref "K1") (pin "A2") (pinfunction "A2_A2") (pintype "passive+no_connect"))
    )
    (net (code "64") (name "unconnected-(SW1-Pad2)") (class "Default")
      (node (ref "SW1") (pin "2") (pinfunction "2_2") (pintype "passive"))
    )
    (net (code "65") (name "unconnected-(SW1-Pad3)") (class "Default")
      (node (ref "SW1") (pin "3") (pinfunction "3_3") (pintype "passive"))
    )
    (net (code "66") (name "unconnected-(SW2-Pad3)") (class "Default")
      (node (ref "SW2") (pin "3") (pinfunction "3_3") (pintype "passive"))
    )
    (net (code "67") (name "unconnected-(SW3-Pad3)") (class "Default")
      (node (ref "SW3") (pin "3") (pinfunction "3_3") (pintype "passive"))
    )
    (net (code "68") (name "unconnected-(SW4-Pad2)") (class "Default")
      (node (ref "SW4") (pin "2") (pinfunction "2_2") (pintype "passive"))
    )
    (net (code "69") (name "unconnected-(SW7-Pad2)") (class "Default")
      (node (ref "SW7") (pin "2") (pinfunction "2_2") (pintype "passive"))
    )
    (net (code "70") (name "unconnected-(SW9-Pad1)") (class "Default")
      (node (ref "SW9") (pin "1") (pinfunction "1_1") (pintype "passive"))
    )
    (net (code "71") (name "unconnected-(SW10-Pad2)") (class "Default")
      (node (ref "SW10") (pin "2") (pinfunction "2_2") (pintype "passive"))
    )
    (net (code "72") (name "unconnected-(U2-RA3{slash}AN3{slash}VREF+{slash}C1IN+-Pad5)") (class "Default")
      (node (ref "U2") (pin "5") (pinfunction "RA3/AN3/VREF+/C1IN+_5") (pintype "bidirectional+no_connect"))
    )
    (net (code "73") (name "unconnected-(U2-RA7{slash}OSC1{slash}CLKIN-Pad13)") (class "Default")
      (node (ref "U2") (pin "13") (pinfunction "RA7/OSC1/CLKIN_13") (pintype "bidirectional+no_connect"))
    )
    (net (code "74") (name "unconnected-(U2-RC0{slash}T1OSO{slash}T1CKI-Pad15)") (class "Default")
      (node (ref "U2") (pin "15") (pinfunction "RC0/T1OSO/T1CKI_15") (pintype "bidirectional+no_connect"))
    )
    (net (code "75") (name "unconnected-(U2-RC1{slash}T1OSI{slash}CCP2-Pad16)") (class "Default")
      (node (ref "U2") (pin "16") (pinfunction "RC1/T1OSI/CCP2_16") (pintype "bidirectional+no_connect"))
    )
    (net (code "76") (name "unconnected-(U2-RC2{slash}P1A{slash}CCP1-Pad17)") (class "Default")
      (node (ref "U2") (pin "17") (pinfunction "RC2/P1A/CCP1_17") (pintype "bidirectional+no_connect"))
    )
    (net (code "77") (name "unconnected-(U2-RC3{slash}SCK{slash}SCL-Pad18)") (class "Default")
      (node (ref "U2") (pin "18") (pinfunction "RC3/SCK/SCL_18") (pintype "bidirectional+no_connect"))
    )
    (net (code "78") (name "unconnected-(U2-RD0-Pad19)") (class "Default")
      (node (ref "U2") (pin "19") (pinfunction "RD0_19") (pintype "bidirectional+no_connect"))
    )
    (net (code "79") (name "unconnected-(U2-RD1-Pad20)") (class "Default")
      (node (ref "U2") (pin "20") (pinfunction "RD1_20") (pintype "bidirectional+no_connect"))
    )
    (net (code "80") (name "unconnected-(U2-RD3-Pad22)") (class "Default")
      (node (ref "U2") (pin "22") (pinfunction "RD3_22") (pintype "bidirectional+no_connect"))
    )
    (net (code "81") (name "unconnected-(U2-RD4-Pad27)") (class "Default")
      (node (ref "U2") (pin "27") (pinfunction "RD4_27") (pintype "bidirectional+no_connect"))
    )
    (net (code "82") (name "unconnected-(U2-RD5{slash}P1B-Pad28)") (class "Default")
      (node (ref "U2") (pin "28") (pinfunction "RD5/P1B_28") (pintype "bidirectional+no_connect"))
    )
    (net (code "83") (name "unconnected-(U2-RD7{slash}P1D-Pad30)") (class "Default")
      (node (ref "U2") (pin "30") (pinfunction "RD7/P1D_30") (pintype "bidirectional+no_connect"))
    )
    (net (code "84") (name "unconnected-(U2-RE0{slash}AN5-Pad8)") (class "Default")
      (node (ref "U2") (pin "8") (pinfunction "RE0/AN5_8") (pintype "bidirectional+no_connect"))
    )
    (net (code "85") (name "unconnected-(U2-RE1{slash}AN6-Pad9)") (class "Default")
      (node (ref "U2") (pin "9") (pinfunction "RE1/AN6_9") (pintype "bidirectional+no_connect"))
    )
    (net (code "86") (name "unconnected-(U2-RE3{slash}~{MCLR}{slash}VPP-Pad1)") (class "Default")
      (node (ref "U2") (pin "1") (pinfunction "RE3/~{MCLR}/VPP_1") (pintype "bidirectional+no_connect"))
    )
    (net (code "87") (name "unconnected-(U2-VDD-Pad11)") (class "Default")
      (node (ref "U2") (pin "11") (pinfunction "VDD_11") (pintype "power_in+no_connect"))
    )
    (net (code "88") (name "unconnected-(U2-VDD-Pad32)") (class "Default")
      (node (ref "U2") (pin "32") (pinfunction "VDD_32") (pintype "power_in+no_connect"))
    )
    (net (code "89") (name "unconnected-(U2-VSS-Pad12)") (class "Default")
      (node (ref "U2") (pin "12") (pinfunction "VSS_12") (pintype "power_in+no_connect"))
    )
    (net (code "90") (name "unconnected-(U2-VSS-Pad31)") (class "Default")
      (node (ref "U2") (pin "31") (pinfunction "VSS_31") (pintype "power_in+no_connect"))
    )
  )
)
